# simreader_marble_perfboard.net
KiCad netlist of a schematic drawn in EAGLE
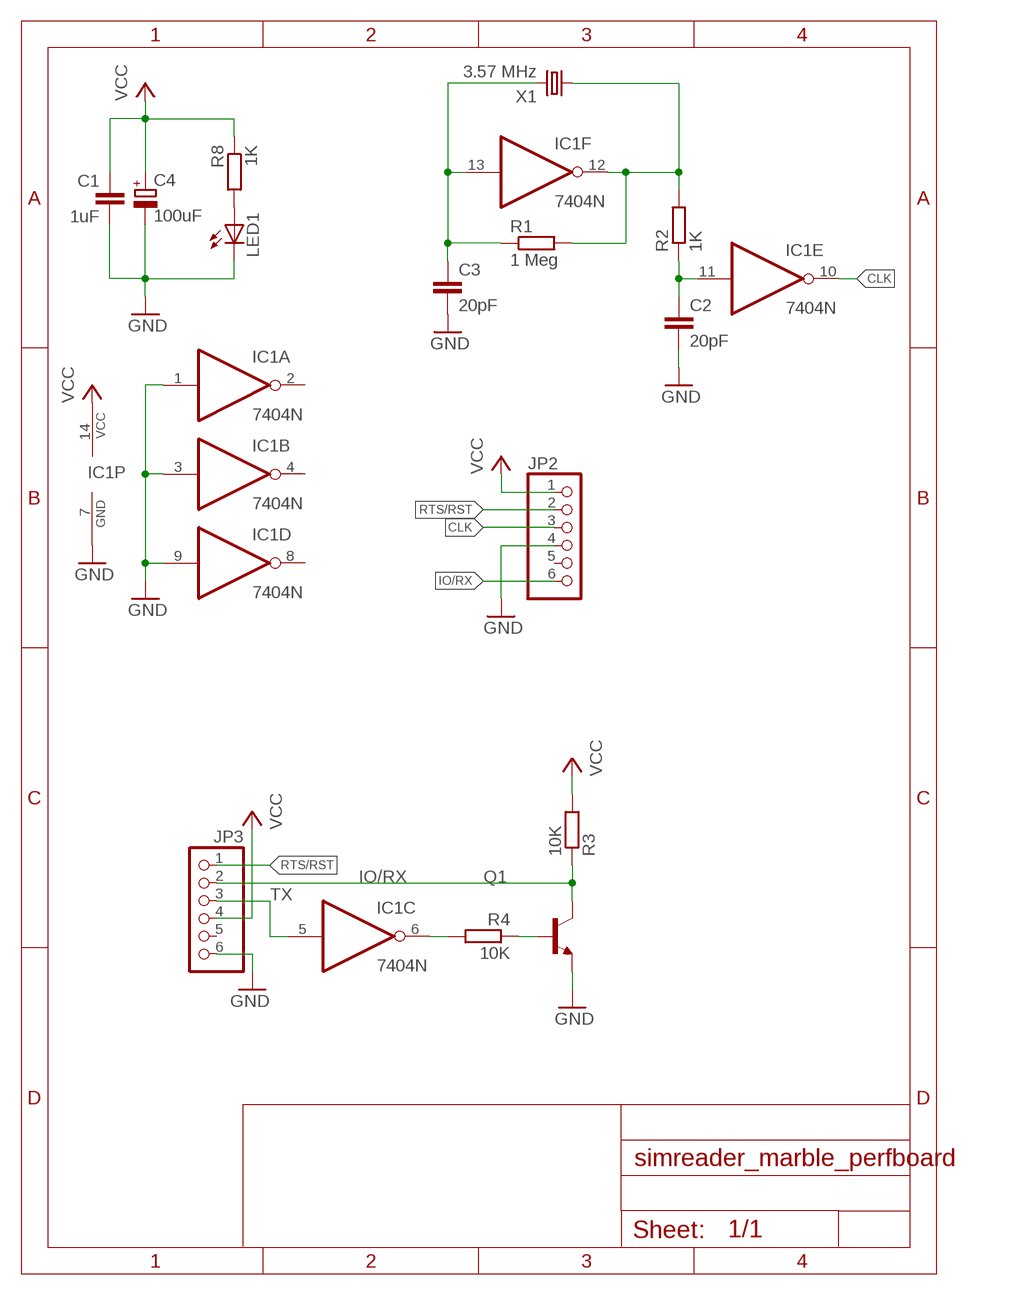
[diagram p0: schematic, sheet 1]

(export (version "E")
  (design (tool "Eeschema 10.0.6"))
  (components
    (comp (ref "C1")
      (value "1uF")
      (footprint "eagle-import:C050-024X044")
      (libsource (lib "eagle-import") (part "C-EU050-024X044"))
    )
    (comp (ref "C2")
      (value "20pF")
      (footprint "eagle-import:C050-024X044")
      (libsource (lib "eagle-import") (part "C-EU050-024X044"))
    )
    (comp (ref "C3")
      (value "20pF")
      (footprint "eagle-import:C050-024X044")
      (libsource (lib "eagle-import") (part "C-EU050-024X044"))
    )
    (comp (ref "C4")
      (value "100uF")
      (footprint "eagle-import:B45181A")
      (libsource (lib "eagle-import") (part "CPOL-EUB45181A"))
    )
    (comp (ref "IC1")
      (value "7404N")
      (footprint "eagle-import:DIL14")
      (libsource (lib "eagle-import") (part "7404N"))
    )
    (comp (ref "JP2")
      (value "PINHD-1X6")
      (footprint "eagle-import:1X06")
      (libsource (lib "eagle-import") (part "PINHD-1X6"))
    )
    (comp (ref "JP3")
      (value "PINHD-1X6")
      (footprint "eagle-import:1X06")
      (libsource (lib "eagle-import") (part "PINHD-1X6"))
    )
    (comp (ref "LED1")
      (value "LED5MM")
      (footprint "eagle-import:LED5MM")
      (libsource (lib "eagle-import") (part "LED5MM"))
    )
    (comp (ref "Q1")
      (value "BC547-NPN-TO92-CBE")
      (footprint "eagle-import:TO92-CBE")
      (libsource (lib "eagle-import") (part "-NPN-TO92-CBEBC547"))
    )
    (comp (ref "R1")
      (value "1 Meg")
      (footprint "eagle-import:0204_7")
      (libsource (lib "eagle-import") (part "R-EU_0204/7"))
    )
    (comp (ref "R2")
      (value "1K")
      (footprint "eagle-import:0204_7")
      (libsource (lib "eagle-import") (part "R-EU_0204/7"))
    )
    (comp (ref "R3")
      (value "10K")
      (footprint "eagle-import:0204_7")
      (libsource (lib "eagle-import") (part "R-EU_0204/7"))
    )
    (comp (ref "R4")
      (value "10K")
      (footprint "eagle-import:0204_7")
      (libsource (lib "eagle-import") (part "R-EU_0204/7"))
    )
    (comp (ref "R8")
      (value "1K")
      (footprint "eagle-import:0204_7")
      (libsource (lib "eagle-import") (part "R-EU_0204/7"))
    )
    (comp (ref "X1")
      (value "3.57 MHz")
      (footprint "eagle-import:HC18U-V")
      (libsource (lib "eagle-import") (part "CRYSTALHC18U-V"))
    )
  )
  (nets
    (net (code "1") (name "/TX") (class "Default")
      (node (ref "IC1") (pin "5") (pinfunction "I_5") (pintype "input"))
      (node (ref "JP3") (pin "3") (pinfunction "3_3") (pintype "passive"))
    )
    (net (code "2") (name "CLK") (class "Default")
      (node (ref "IC1") (pin "10") (pinfunction "O_10") (pintype "output"))
      (node (ref "JP2") (pin "3") (pinfunction "3_3") (pintype "passive"))
    )
    (net (code "3") (name "GND") (class "Default")
      (node (ref "C1") (pin "2") (pinfunction "2_2") (pintype "passive"))
      (node (ref "C2") (pin "2") (pinfunction "2_2") (pintype "passive"))
      (node (ref "C3") (pin "2") (pinfunction "2_2") (pintype "passive"))
      (node (ref "C4") (pin "-") (pinfunction "-_-") (pintype "passive"))
      (node (ref "IC1") (pin "1") (pinfunction "I_1") (pintype "input"))
      (node (ref "IC1") (pin "3") (pinfunction "I_3") (pintype "input"))
      (node (ref "IC1") (pin "7") (pinfunction "GND_7") (pintype "power_in"))
      (node (ref "IC1") (pin "9") (pinfunction "I_9") (pintype "input"))
      (node (ref "JP2") (pin "4") (pinfunction "4_4") (pintype "passive"))
      (node (ref "JP3") (pin "6") (pinfunction "6_6") (pintype "passive"))
      (node (ref "LED1") (pin "K") (pinfunction "C_K") (pintype "passive"))
      (node (ref "Q1") (pin "E") (pinfunction "E_E") (pintype "passive"))
    )
    (net (code "4") (name "IO{slash}RX") (class "Default")
      (node (ref "JP2") (pin "6") (pinfunction "6_6") (pintype "passive"))
      (node (ref "JP3") (pin "2") (pinfunction "2_2") (pintype "passive"))
      (node (ref "Q1") (pin "C") (pinfunction "C_C") (pintype "passive"))
      (node (ref "R3") (pin "1") (pinfunction "1_1") (pintype "passive"))
    )
    (net (code "5") (name "Net-(IC1C-O)") (class "Default")
      (node (ref "IC1") (pin "6") (pinfunction "O_6") (pintype "output"))
      (node (ref "R4") (pin "2") (pinfunction "2_2") (pintype "passive"))
    )
    (net (code "6") (name "Net-(IC1E-I)") (class "Default")
      (node (ref "C2") (pin "1") (pinfunction "1_1") (pintype "passive"))
      (node (ref "IC1") (pin "11") (pinfunction "I_11") (pintype "input"))
      (node (ref "R2") (pin "1") (pinfunction "1_1") (pintype "passive"))
    )
    (net (code "7") (name "Net-(IC1F-I)") (class "Default")
      (node (ref "C3") (pin "1") (pinfunction "1_1") (pintype "passive"))
      (node (ref "IC1") (pin "13") (pinfunction "I_13") (pintype "input"))
      (node (ref "R1") (pin "1") (pinfunction "1_1") (pintype "passive"))
      (node (ref "X1") (pin "2") (pinfunction "2_2") (pintype "passive"))
    )
    (net (code "8") (name "Net-(IC1F-O)") (class "Default")
      (node (ref "IC1") (pin "12") (pinfunction "O_12") (pintype "output"))
      (node (ref "R1") (pin "2") (pinfunction "2_2") (pintype "passive"))
      (node (ref "R2") (pin "2") (pinfunction "2_2") (pintype "passive"))
      (node (ref "X1") (pin "1") (pinfunction "1_1") (pintype "passive"))
    )
    (net (code "9") (name "Net-(LED1-PadA)") (class "Default")
      (node (ref "LED1") (pin "A") (pinfunction "A_A") (pintype "passive"))
      (node (ref "R8") (pin "2") (pinfunction "2_2") (pintype "passive"))
    )
    (net (code "10") (name "Net-(Q1-PadB)") (class "Default")
      (node (ref "Q1") (pin "B") (pinfunction "B_B") (pintype "passive"))
      (node (ref "R4") (pin "1") (pinfunction "1_1") (pintype "passive"))
    )
    (net (code "11") (name "RTS{slash}RST") (class "Default")
      (node (ref "JP2") (pin "2") (pinfunction "2_2") (pintype "passive"))
      (node (ref "JP3") (pin "1") (pinfunction "1_1") (pintype "passive"))
    )
    (net (code "12") (name "VCC") (class "Default")
      (node (ref "C1") (pin "1") (pinfunction "1_1") (pintype "passive"))
      (node (ref "C4") (pin "+") (pinfunction "+_+") (pintype "passive"))
      (node (ref "IC1") (pin "14") (pinfunction "VCC_14") (pintype "power_in"))
      (node (ref "JP2") (pin "1") (pinfunction "1_1") (pintype "passive"))
      (node (ref "JP3") (pin "4") (pinfunction "4_4") (pintype "passive"))
      (node (ref "R3") (pin "2") (pinfunction "2_2") (pintype "passive"))
      (node (ref "R8") (pin "1") (pinfunction "1_1") (pintype "passive"))
    )
    (net (code "13") (name "unconnected-(IC1A-O-Pad2)") (class "Default")
      (node (ref "IC1") (pin "2") (pinfunction "O_2") (pintype "output"))
    )
    (net (code "14") (name "unconnected-(IC1B-O-Pad4)") (class "Default")
      (node (ref "IC1") (pin "4") (pinfunction "O_4") (pintype "output"))
    )
    (net (code "15") (name "unconnected-(IC1D-O-Pad8)") (class "Default")
      (node (ref "IC1") (pin "8") (pinfunction "O_8") (pintype "output"))
    )
    (net (code "16") (name "unconnected-(JP2-Pad5)") (class "Default")
      (node (ref "JP2") (pin "5") (pinfunction "5_5") (pintype "passive"))
    )
    (net (code "17") (name "unconnected-(JP3-Pad5)") (class "Default")
      (node (ref "JP3") (pin "5") (pinfunction "5_5") (pintype "passive"))
    )
  )
)
